# MOSFETs_and_Driver.net
KiCad netlist of a schematic drawn in Altium Designer
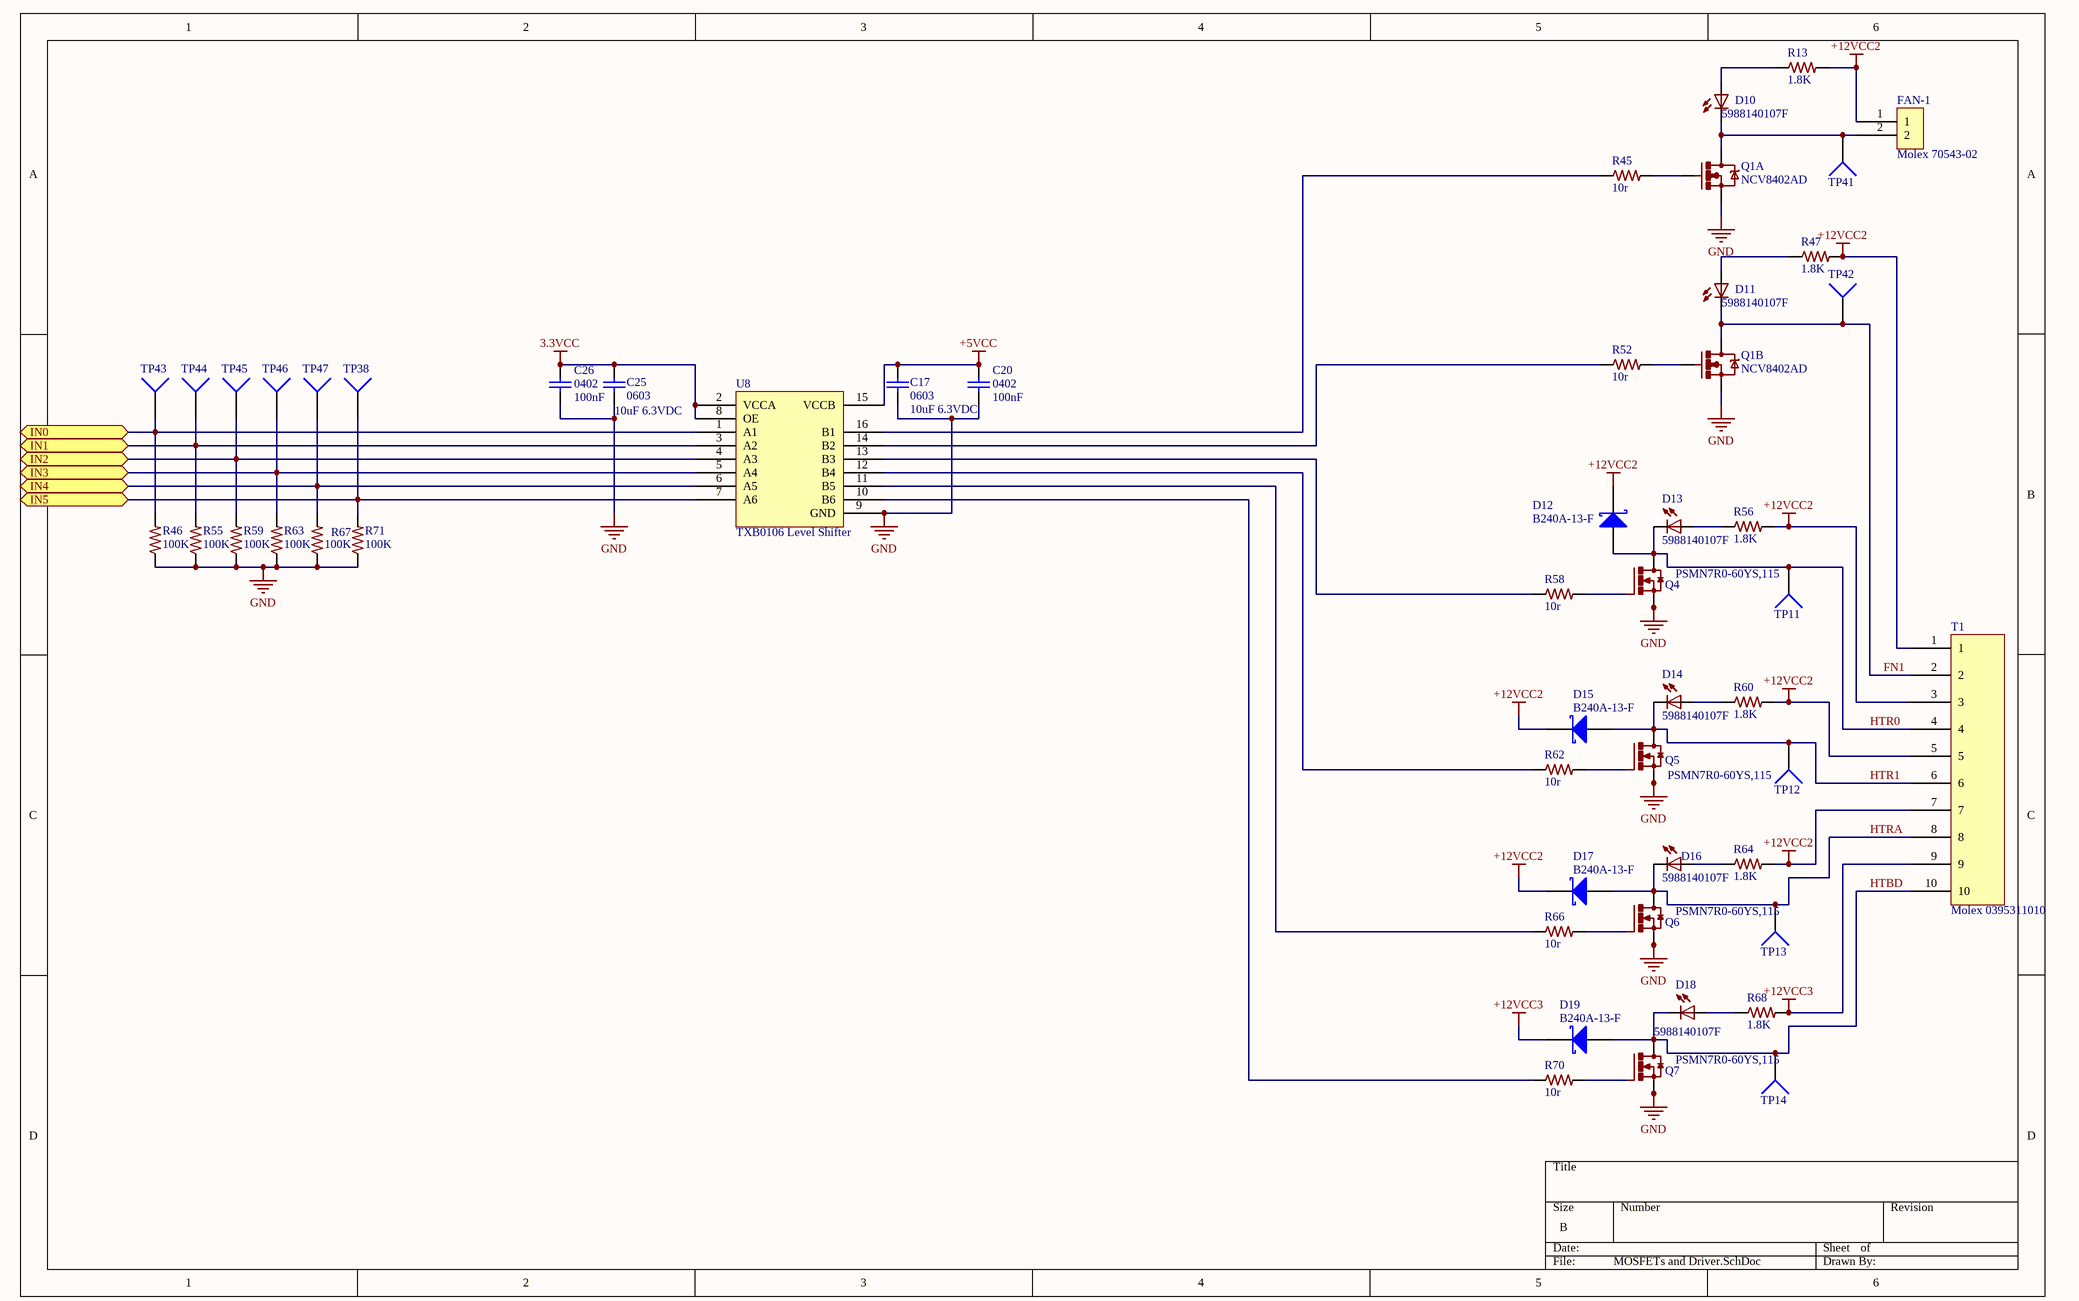
[diagram p0: MOSFETs and Driver.SchDoc]

(export (version "E")
  (design (tool "Eeschema 10.0.6"))
  (components
    (comp (ref "C17")
      (value "0603")
      (footprint "C0603")
      (description "CAP CER 10UF 6.3V 10% JB 0603")
      (fields
        (field (name "MFR PART #") "C1608JB0J106K080AB")
        (field (name "MFR") "TDK")
        (field (name "ALTIUM_VALUE") "10uF 6.3VDC")
      )
      (libsource (lib "Tigershark3D") (part "C1608JB0J106K080AB"))
    )
    (comp (ref "C20")
      (value "100nF")
      (footprint "C0402")
      (description "CAP CER 0.1UF (100nF) 16V 10% X7R 0402")
      (fields
        (field (name "MFR PART #") "GRM155R71C104KA88D")
        (field (name "MFR") "Murata")
        (field (name "PACKAGEREFERENCE") "0402")
        (field (name "PUBLISHER") "Ultimachine")
      )
      (libsource (lib "Tigershark3D") (part "GRM155R71C104KA88D"))
    )
    (comp (ref "C25")
      (value "0603")
      (footprint "C0603")
      (description "CAP CER 10UF 6.3V 10% JB 0603")
      (fields
        (field (name "MFR PART #") "C1608JB0J106K080AB")
        (field (name "MFR") "TDK")
        (field (name "ALTIUM_VALUE") "10uF 6.3VDC")
      )
      (libsource (lib "Tigershark3D") (part "C1608JB0J106K080AB"))
    )
    (comp (ref "C26")
      (value "100nF")
      (footprint "C0402")
      (description "CAP CER 0.1UF (100nF) 16V 10% X7R 0402")
      (fields
        (field (name "MFR PART #") "GRM155R71C104KA88D")
        (field (name "MFR") "Murata")
        (field (name "PACKAGEREFERENCE") "0402")
        (field (name "PUBLISHER") "Ultimachine")
      )
      (libsource (lib "Tigershark3D") (part "GRM155R71C104KA88D"))
    )
    (comp (ref "D10")
      (value "5988140107F")
      (footprint "LED2012120")
      (description "LED 0805 Yellow")
      (fields (field (name "PUBLISHER") "UltiMachine"))
      (libsource (lib "Tigershark3D") (part "5988140107F"))
    )
    (comp (ref "D11")
      (value "5988140107F")
      (footprint "LED2012120")
      (description "LED 0805 Yellow")
      (fields (field (name "PUBLISHER") "UltiMachine"))
      (libsource (lib "Tigershark3D") (part "5988140107F"))
    )
    (comp (ref "D12")
      (value "B240A-13-F")
      (footprint "SK310A-TP")
      (description "Schottky Diode")
      (fields (field (name "PUBLISHER") "Altium Limited"))
      (libsource (lib "Miscellaneous Devices") (part "D Schottky"))
    )
    (comp (ref "D13")
      (value "5988140107F")
      (footprint "LED2012120")
      (description "LED 0805 Yellow")
      (fields (field (name "PUBLISHER") "UltiMachine"))
      (libsource (lib "Tigershark3D") (part "5988140107F"))
    )
    (comp (ref "D14")
      (value "5988140107F")
      (footprint "LED2012120")
      (description "LED 0805 Yellow")
      (fields (field (name "PUBLISHER") "UltiMachine"))
      (libsource (lib "Tigershark3D") (part "5988140107F"))
    )
    (comp (ref "D15")
      (value "B240A-13-F")
      (footprint "SK310A-TP")
      (description "Schottky Diode")
      (fields (field (name "PUBLISHER") "Altium Limited"))
      (libsource (lib "Miscellaneous Devices") (part "D Schottky"))
    )
    (comp (ref "D16")
      (value "5988140107F")
      (footprint "LED2012120")
      (description "LED 0805 Yellow")
      (fields (field (name "PUBLISHER") "UltiMachine"))
      (libsource (lib "Tigershark3D") (part "5988140107F"))
    )
    (comp (ref "D17")
      (value "B240A-13-F")
      (footprint "SK310A-TP")
      (description "Schottky Diode")
      (fields (field (name "PUBLISHER") "Altium Limited"))
      (libsource (lib "Miscellaneous Devices") (part "D Schottky"))
    )
    (comp (ref "D18")
      (value "5988140107F")
      (footprint "LED2012120")
      (description "LED 0805 Yellow")
      (fields (field (name "PUBLISHER") "UltiMachine"))
      (libsource (lib "Tigershark3D") (part "5988140107F"))
    )
    (comp (ref "D19")
      (value "B240A-13-F")
      (footprint "SK310A-TP")
      (description "Schottky Diode")
      (fields (field (name "PUBLISHER") "Altium Limited"))
      (libsource (lib "Miscellaneous Devices") (part "D Schottky"))
    )
    (comp (ref "FAN-1")
      (value "Molex 70543-02")
      (footprint "70543-02")
      (libsource (lib "ZMBo Schematic Library") (part "Molex 70543-02"))
    )
    (comp (ref "Q1")
      (value "NCV8402AD")
      (footprint "NCV8402AD-SOIC8")
      (libsource (lib "3Delight") (part "NCV8402AD"))
    )
    (comp (ref "Q4")
      (value "PSMN7R0-60YS,115")
      (footprint "SOT669")
      (description "Mosfet N-channel 60V 356A 117W 9.3mOhms")
      (fields (field (name "PUBLISHER") "UltiMachine"))
      (libsource (lib "3Delight") (part "PSMN7R0-60YS,115"))
    )
    (comp (ref "Q5")
      (value "PSMN7R0-60YS,115")
      (footprint "SOT669")
      (description "Mosfet N-channel 60V 356A 117W 9.3mOhms")
      (fields (field (name "PUBLISHER") "UltiMachine"))
      (libsource (lib "3Delight") (part "PSMN7R0-60YS,115"))
    )
    (comp (ref "Q6")
      (value "PSMN7R0-60YS,115")
      (footprint "SOT669")
      (description "Mosfet N-channel 60V 356A 117W 9.3mOhms")
      (fields (field (name "PUBLISHER") "UltiMachine"))
      (libsource (lib "3Delight") (part "PSMN7R0-60YS,115"))
    )
    (comp (ref "Q7")
      (value "PSMN7R0-60YS,115")
      (footprint "SOT669")
      (description "Mosfet N-channel 60V 356A 117W 9.3mOhms")
      (fields (field (name "PUBLISHER") "UltiMachine"))
      (libsource (lib "3Delight") (part "PSMN7R0-60YS,115"))
    )
    (comp (ref "R13")
      (value "1.8K")
      (footprint "R0603")
      (description "RES 0603 1.8K 100mW 5%")
      (fields
        (field (name "MANUFACTURERPARTNUMBER") "RC0603JR-071K8L")
        (field (name "PUBLISHER") "UltiMachine")
      )
      (libsource (lib "Tigershark3D") (part "RC0603JR-071K8L"))
    )
    (comp (ref "R45")
      (value "10r")
      (footprint "R0603")
      (description "RES 0603 10r 100mW 1%")
      (fields
        (field (name "MANUFACTURERPARTNUMBER") "CRCW060310R0FKEA")
        (field (name "PUBLISHER") "UltiMachine")
      )
      (libsource (lib "Tigershark3D") (part "CRCW060310R0FKEA"))
    )
    (comp (ref "R46")
      (value "100K")
      (footprint "R0402")
      (description "RES SMD 100K OHM 1% 1/16W 0402")
      (fields
        (field (name "MANUFACTURER") "Samsung")
        (field (name "MANUFACTURERPARTNUMBER") "RC1005F104CS")
        (field (name "PUBLISHER") "UltiMachine")
      )
      (libsource (lib "Tigershark3D") (part "RC1005F104CS"))
    )
    (comp (ref "R47")
      (value "1.8K")
      (footprint "R0603")
      (description "RES 0603 1.8K 100mW 5%")
      (fields
        (field (name "MANUFACTURERPARTNUMBER") "RC0603JR-071K8L")
        (field (name "PUBLISHER") "UltiMachine")
      )
      (libsource (lib "Tigershark3D") (part "RC0603JR-071K8L"))
    )
    (comp (ref "R52")
      (value "10r")
      (footprint "R0603")
      (description "RES 0603 10r 100mW 1%")
      (fields
        (field (name "MANUFACTURERPARTNUMBER") "CRCW060310R0FKEA")
        (field (name "PUBLISHER") "UltiMachine")
      )
      (libsource (lib "Tigershark3D") (part "CRCW060310R0FKEA"))
    )
    (comp (ref "R55")
      (value "100K")
      (footprint "R0402")
      (description "RES SMD 100K OHM 1% 1/16W 0402")
      (fields
        (field (name "MANUFACTURER") "Samsung")
        (field (name "MANUFACTURERPARTNUMBER") "RC1005F104CS")
        (field (name "PUBLISHER") "UltiMachine")
      )
      (libsource (lib "Tigershark3D") (part "RC1005F104CS"))
    )
    (comp (ref "R56")
      (value "1.8K")
      (footprint "R0603")
      (description "RES 0603 1.8K 100mW 5%")
      (fields
        (field (name "MANUFACTURERPARTNUMBER") "RC0603JR-071K8L")
        (field (name "PUBLISHER") "UltiMachine")
      )
      (libsource (lib "Tigershark3D") (part "RC0603JR-071K8L"))
    )
    (comp (ref "R58")
      (value "10r")
      (footprint "R0603")
      (description "RES 0603 10r 100mW 1%")
      (fields
        (field (name "MANUFACTURERPARTNUMBER") "CRCW060310R0FKEA")
        (field (name "PUBLISHER") "UltiMachine")
      )
      (libsource (lib "Tigershark3D") (part "CRCW060310R0FKEA"))
    )
    (comp (ref "R59")
      (value "100K")
      (footprint "R0402")
      (description "RES SMD 100K OHM 1% 1/16W 0402")
      (fields
        (field (name "MANUFACTURER") "Samsung")
        (field (name "MANUFACTURERPARTNUMBER") "RC1005F104CS")
        (field (name "PUBLISHER") "UltiMachine")
      )
      (libsource (lib "Tigershark3D") (part "RC1005F104CS"))
    )
    (comp (ref "R60")
      (value "1.8K")
      (footprint "R0603")
      (description "RES 0603 1.8K 100mW 5%")
      (fields
        (field (name "MANUFACTURERPARTNUMBER") "RC0603JR-071K8L")
        (field (name "PUBLISHER") "UltiMachine")
      )
      (libsource (lib "Tigershark3D") (part "RC0603JR-071K8L"))
    )
    (comp (ref "R62")
      (value "10r")
      (footprint "R0603")
      (description "RES 0603 10r 100mW 1%")
      (fields
        (field (name "MANUFACTURERPARTNUMBER") "CRCW060310R0FKEA")
        (field (name "PUBLISHER") "UltiMachine")
      )
      (libsource (lib "Tigershark3D") (part "CRCW060310R0FKEA"))
    )
    (comp (ref "R63")
      (value "100K")
      (footprint "R0402")
      (description "RES SMD 100K OHM 1% 1/16W 0402")
      (fields
        (field (name "MANUFACTURER") "Samsung")
        (field (name "MANUFACTURERPARTNUMBER") "RC1005F104CS")
        (field (name "PUBLISHER") "UltiMachine")
      )
      (libsource (lib "Tigershark3D") (part "RC1005F104CS"))
    )
    (comp (ref "R64")
      (value "1.8K")
      (footprint "R0603")
      (description "RES 0603 1.8K 100mW 5%")
      (fields
        (field (name "MANUFACTURERPARTNUMBER") "RC0603JR-071K8L")
        (field (name "PUBLISHER") "UltiMachine")
      )
      (libsource (lib "Tigershark3D") (part "RC0603JR-071K8L"))
    )
    (comp (ref "R66")
      (value "10r")
      (footprint "R0603")
      (description "RES 0603 10r 100mW 1%")
      (fields
        (field (name "MANUFACTURERPARTNUMBER") "CRCW060310R0FKEA")
        (field (name "PUBLISHER") "UltiMachine")
      )
      (libsource (lib "Tigershark3D") (part "CRCW060310R0FKEA"))
    )
    (comp (ref "R67")
      (value "100K")
      (footprint "R0402")
      (description "RES SMD 100K OHM 1% 1/16W 0402")
      (fields
        (field (name "MANUFACTURER") "Samsung")
        (field (name "MANUFACTURERPARTNUMBER") "RC1005F104CS")
        (field (name "PUBLISHER") "UltiMachine")
      )
      (libsource (lib "Tigershark3D") (part "RC1005F104CS"))
    )
    (comp (ref "R68")
      (value "1.8K")
      (footprint "R0603")
      (description "RES 0603 1.8K 100mW 5%")
      (fields
        (field (name "MANUFACTURERPARTNUMBER") "RC0603JR-071K8L")
        (field (name "PUBLISHER") "UltiMachine")
      )
      (libsource (lib "Tigershark3D") (part "RC0603JR-071K8L"))
    )
    (comp (ref "R70")
      (value "10r")
      (footprint "R0603")
      (description "RES 0603 10r 100mW 1%")
      (fields
        (field (name "MANUFACTURERPARTNUMBER") "CRCW060310R0FKEA")
        (field (name "PUBLISHER") "UltiMachine")
      )
      (libsource (lib "Tigershark3D") (part "CRCW060310R0FKEA"))
    )
    (comp (ref "R71")
      (value "100K")
      (footprint "R0402")
      (description "RES SMD 100K OHM 1% 1/16W 0402")
      (fields
        (field (name "MANUFACTURER") "Samsung")
        (field (name "MANUFACTURERPARTNUMBER") "RC1005F104CS")
        (field (name "PUBLISHER") "UltiMachine")
      )
      (libsource (lib "Tigershark3D") (part "RC1005F104CS"))
    )
    (comp (ref "T1")
      (value "Molex 0395311010")
      (footprint "MSTBV10")
      (description "MSBTV10 10 port connector same as RAMBo")
      (fields (field (name "PART NUMBER") "0395311010"))
      (libsource (lib "Tigershark3D") (part "0395311010 - Molex 10 Position Connector"))
    )
    (comp (ref "TP11")
      (value "TP4")
      (footprint "TP-2")
      (description "Socket")
      (fields (field (name "PUBLISHER") "Altium Limited"))
      (libsource (lib "ZMBo Schematic Library") (part "Socket"))
    )
    (comp (ref "TP12")
      (value "TP4")
      (footprint "TP-2")
      (description "Socket")
      (fields (field (name "PUBLISHER") "Altium Limited"))
      (libsource (lib "ZMBo Schematic Library") (part "Socket"))
    )
    (comp (ref "TP13")
      (value "TP4")
      (footprint "TP-2")
      (description "Socket")
      (fields (field (name "PUBLISHER") "Altium Limited"))
      (libsource (lib "ZMBo Schematic Library") (part "Socket"))
    )
    (comp (ref "TP14")
      (value "TP4")
      (footprint "TP-2")
      (description "Socket")
      (fields (field (name "PUBLISHER") "Altium Limited"))
      (libsource (lib "ZMBo Schematic Library") (part "Socket"))
    )
    (comp (ref "TP38")
      (value "TP4")
      (footprint "TP-2")
      (description "Socket")
      (fields (field (name "PUBLISHER") "Altium Limited"))
      (libsource (lib "ZMBo Schematic Library") (part "Socket"))
    )
    (comp (ref "TP41")
      (value "TP4")
      (footprint "TP-2")
      (description "Socket")
      (fields (field (name "PUBLISHER") "Altium Limited"))
      (libsource (lib "ZMBo Schematic Library") (part "Socket"))
    )
    (comp (ref "TP42")
      (value "TP4")
      (footprint "TP-2")
      (description "Socket")
      (fields (field (name "PUBLISHER") "Altium Limited"))
      (libsource (lib "ZMBo Schematic Library") (part "Socket"))
    )
    (comp (ref "TP43")
      (value "TP4")
      (footprint "TP-2")
      (description "Socket")
      (fields (field (name "PUBLISHER") "Altium Limited"))
      (libsource (lib "ZMBo Schematic Library") (part "Socket"))
    )
    (comp (ref "TP44")
      (value "TP4")
      (footprint "TP-2")
      (description "Socket")
      (fields (field (name "PUBLISHER") "Altium Limited"))
      (libsource (lib "ZMBo Schematic Library") (part "Socket"))
    )
    (comp (ref "TP45")
      (value "TP4")
      (footprint "TP-2")
      (description "Socket")
      (fields (field (name "PUBLISHER") "Altium Limited"))
      (libsource (lib "ZMBo Schematic Library") (part "Socket"))
    )
    (comp (ref "TP46")
      (value "TP4")
      (footprint "TP-2")
      (description "Socket")
      (fields (field (name "PUBLISHER") "Altium Limited"))
      (libsource (lib "ZMBo Schematic Library") (part "Socket"))
    )
    (comp (ref "TP47")
      (value "TP4")
      (footprint "TP-2")
      (description "Socket")
      (fields (field (name "PUBLISHER") "Altium Limited"))
      (libsource (lib "ZMBo Schematic Library") (part "Socket"))
    )
    (comp (ref "U8")
      (value "TXB0106 Level Shifter")
      (footprint "TSOP65P640X120-16N")
      (description "TXB0106 - Bidriectional Opendrain/pushpull level shift")
      (libsource (lib "ZMBo Schematic Library") (part "TXB0106"))
    )
  )
  (nets
    (net (code "1") (name "+5VCC") (class "Default")
      (node (ref "C17") (pin "2") (pinfunction "2_2") (pintype "passive"))
      (node (ref "C20") (pin "2") (pinfunction "2_2") (pintype "passive"))
      (node (ref "U8") (pin "15") (pinfunction "VCCB_15") (pintype "passive"))
    )
    (net (code "2") (name "+12VCC2") (class "Default")
      (node (ref "D12") (pin "2") (pinfunction "K_2") (pintype "passive"))
      (node (ref "D15") (pin "2") (pinfunction "K_2") (pintype "passive"))
      (node (ref "D17") (pin "2") (pinfunction "K_2") (pintype "passive"))
      (node (ref "FAN-1") (pin "1") (pinfunction "1_1") (pintype "passive"))
      (node (ref "R13") (pin "2") (pinfunction "2_2") (pintype "passive"))
      (node (ref "R47") (pin "2") (pinfunction "2_2") (pintype "passive"))
      (node (ref "R56") (pin "2") (pinfunction "2_2") (pintype "passive"))
      (node (ref "R60") (pin "2") (pinfunction "2_2") (pintype "passive"))
      (node (ref "R64") (pin "2") (pinfunction "2_2") (pintype "passive"))
      (node (ref "T1") (pin "1") (pinfunction "1_1") (pintype "passive"))
      (node (ref "T1") (pin "3") (pinfunction "3_3") (pintype "passive"))
      (node (ref "T1") (pin "5") (pinfunction "5_5") (pintype "passive"))
      (node (ref "T1") (pin "7") (pinfunction "7_7") (pintype "passive"))
    )
    (net (code "3") (name "+12VCC3") (class "Default")
      (node (ref "D19") (pin "2") (pinfunction "K_2") (pintype "passive"))
      (node (ref "R68") (pin "2") (pinfunction "2_2") (pintype "passive"))
      (node (ref "T1") (pin "9") (pinfunction "9_9") (pintype "passive"))
    )
    (net (code "4") (name "/FN1") (class "Default")
      (node (ref "D11") (pin "C") (pinfunction "C_C") (pintype "passive"))
      (node (ref "Q1") (pin "5") (pinfunction "D_5") (pintype "passive"))
      (node (ref "T1") (pin "2") (pinfunction "2_2") (pintype "passive"))
      (node (ref "TP42") (pin "1") (pinfunction "1_1") (pintype "passive"))
    )
    (net (code "5") (name "/HTBD") (class "Default")
      (node (ref "D18") (pin "C") (pinfunction "C_C") (pintype "passive"))
      (node (ref "D19") (pin "1") (pinfunction "A_1") (pintype "passive"))
      (node (ref "Q7") (pin "MB") (pinfunction "D_MB") (pintype "passive"))
      (node (ref "T1") (pin "10") (pinfunction "10_10") (pintype "passive"))
      (node (ref "TP14") (pin "1") (pinfunction "1_1") (pintype "passive"))
    )
    (net (code "6") (name "/HTR0") (class "Default")
      (node (ref "D12") (pin "1") (pinfunction "A_1") (pintype "passive"))
      (node (ref "D13") (pin "C") (pinfunction "C_C") (pintype "passive"))
      (node (ref "Q4") (pin "MB") (pinfunction "D_MB") (pintype "passive"))
      (node (ref "T1") (pin "4") (pinfunction "4_4") (pintype "passive"))
      (node (ref "TP11") (pin "1") (pinfunction "1_1") (pintype "passive"))
    )
    (net (code "7") (name "/HTR1") (class "Default")
      (node (ref "D14") (pin "C") (pinfunction "C_C") (pintype "passive"))
      (node (ref "D15") (pin "1") (pinfunction "A_1") (pintype "passive"))
      (node (ref "Q5") (pin "MB") (pinfunction "D_MB") (pintype "passive"))
      (node (ref "T1") (pin "6") (pinfunction "6_6") (pintype "passive"))
      (node (ref "TP12") (pin "1") (pinfunction "1_1") (pintype "passive"))
    )
    (net (code "8") (name "/HTRA") (class "Default")
      (node (ref "D16") (pin "C") (pinfunction "C_C") (pintype "passive"))
      (node (ref "D17") (pin "1") (pinfunction "A_1") (pintype "passive"))
      (node (ref "Q6") (pin "MB") (pinfunction "D_MB") (pintype "passive"))
      (node (ref "T1") (pin "8") (pinfunction "8_8") (pintype "passive"))
      (node (ref "TP13") (pin "1") (pinfunction "1_1") (pintype "passive"))
    )
    (net (code "9") (name "/IN0") (class "Default")
      (node (ref "R46") (pin "2") (pinfunction "2_2") (pintype "passive"))
      (node (ref "TP43") (pin "1") (pinfunction "1_1") (pintype "passive"))
      (node (ref "U8") (pin "1") (pinfunction "A1_1") (pintype "passive"))
    )
    (net (code "10") (name "/IN1") (class "Default")
      (node (ref "R55") (pin "2") (pinfunction "2_2") (pintype "passive"))
      (node (ref "TP44") (pin "1") (pinfunction "1_1") (pintype "passive"))
      (node (ref "U8") (pin "3") (pinfunction "A2_3") (pintype "passive"))
    )
    (net (code "11") (name "/IN2") (class "Default")
      (node (ref "R59") (pin "2") (pinfunction "2_2") (pintype "passive"))
      (node (ref "TP45") (pin "1") (pinfunction "1_1") (pintype "passive"))
      (node (ref "U8") (pin "4") (pinfunction "A3_4") (pintype "passive"))
    )
    (net (code "12") (name "/IN3") (class "Default")
      (node (ref "R63") (pin "2") (pinfunction "2_2") (pintype "passive"))
      (node (ref "TP46") (pin "1") (pinfunction "1_1") (pintype "passive"))
      (node (ref "U8") (pin "5") (pinfunction "A4_5") (pintype "passive"))
    )
    (net (code "13") (name "/IN4") (class "Default")
      (node (ref "R67") (pin "2") (pinfunction "2_2") (pintype "passive"))
      (node (ref "TP47") (pin "1") (pinfunction "1_1") (pintype "passive"))
      (node (ref "U8") (pin "6") (pinfunction "A5_6") (pintype "passive"))
    )
    (net (code "14") (name "/IN5") (class "Default")
      (node (ref "R71") (pin "2") (pinfunction "2_2") (pintype "passive"))
      (node (ref "TP38") (pin "1") (pinfunction "1_1") (pintype "passive"))
      (node (ref "U8") (pin "7") (pinfunction "A6_7") (pintype "passive"))
    )
    (net (code "15") (name "3.3VCC") (class "Default")
      (node (ref "C25") (pin "2") (pinfunction "2_2") (pintype "passive"))
      (node (ref "C26") (pin "2") (pinfunction "2_2") (pintype "passive"))
      (node (ref "U8") (pin "2") (pinfunction "VCCA_2") (pintype "passive"))
      (node (ref "U8") (pin "8") (pinfunction "OE_8") (pintype "passive"))
    )
    (net (code "16") (name "GND") (class "Default")
      (node (ref "C17") (pin "1") (pinfunction "1_1") (pintype "passive"))
      (node (ref "C20") (pin "1") (pinfunction "1_1") (pintype "passive"))
      (node (ref "C25") (pin "1") (pinfunction "1_1") (pintype "passive"))
      (node (ref "C26") (pin "1") (pinfunction "1_1") (pintype "passive"))
      (node (ref "Q1") (pin "1") (pinfunction "S_1") (pintype "passive"))
      (node (ref "Q1") (pin "3") (pinfunction "S_3") (pintype "passive"))
      (node (ref "Q4") (pin "1") (pinfunction "S_1") (pintype "passive"))
      (node (ref "Q4") (pin "2") (pinfunction "S_2") (pintype "passive"))
      (node (ref "Q4") (pin "3") (pinfunction "S_3") (pintype "passive"))
      (node (ref "Q5") (pin "1") (pinfunction "S_1") (pintype "passive"))
      (node (ref "Q5") (pin "2") (pinfunction "S_2") (pintype "passive"))
      (node (ref "Q5") (pin "3") (pinfunction "S_3") (pintype "passive"))
      (node (ref "Q6") (pin "1") (pinfunction "S_1") (pintype "passive"))
      (node (ref "Q6") (pin "2") (pinfunction "S_2") (pintype "passive"))
      (node (ref "Q6") (pin "3") (pinfunction "S_3") (pintype "passive"))
      (node (ref "Q7") (pin "1") (pinfunction "S_1") (pintype "passive"))
      (node (ref "Q7") (pin "2") (pinfunction "S_2") (pintype "passive"))
      (node (ref "Q7") (pin "3") (pinfunction "S_3") (pintype "passive"))
      (node (ref "R46") (pin "1") (pinfunction "1_1") (pintype "passive"))
      (node (ref "R55") (pin "1") (pinfunction "1_1") (pintype "passive"))
      (node (ref "R59") (pin "1") (pinfunction "1_1") (pintype "passive"))
      (node (ref "R63") (pin "1") (pinfunction "1_1") (pintype "passive"))
      (node (ref "R67") (pin "1") (pinfunction "1_1") (pintype "passive"))
      (node (ref "R71") (pin "1") (pinfunction "1_1") (pintype "passive"))
      (node (ref "U8") (pin "9") (pinfunction "GND_9") (pintype "passive"))
    )
    (net (code "17") (name "Net-(D10-PadA)") (class "Default")
      (node (ref "D10") (pin "A") (pinfunction "A_A") (pintype "passive"))
      (node (ref "R13") (pin "1") (pinfunction "1_1") (pintype "passive"))
    )
    (net (code "18") (name "Net-(D11-PadA)") (class "Default")
      (node (ref "D11") (pin "A") (pinfunction "A_A") (pintype "passive"))
      (node (ref "R47") (pin "1") (pinfunction "1_1") (pintype "passive"))
    )
    (net (code "19") (name "Net-(D13-PadA)") (class "Default")
      (node (ref "D13") (pin "A") (pinfunction "A_A") (pintype "passive"))
      (node (ref "R56") (pin "1") (pinfunction "1_1") (pintype "passive"))
    )
    (net (code "20") (name "Net-(D14-PadA)") (class "Default")
      (node (ref "D14") (pin "A") (pinfunction "A_A") (pintype "passive"))
      (node (ref "R60") (pin "1") (pinfunction "1_1") (pintype "passive"))
    )
    (net (code "21") (name "Net-(D16-PadA)") (class "Default")
      (node (ref "D16") (pin "A") (pinfunction "A_A") (pintype "passive"))
      (node (ref "R64") (pin "1") (pinfunction "1_1") (pintype "passive"))
    )
    (net (code "22") (name "Net-(D18-PadA)") (class "Default")
      (node (ref "D18") (pin "A") (pinfunction "A_A") (pintype "passive"))
      (node (ref "R68") (pin "1") (pinfunction "1_1") (pintype "passive"))
    )
    (net (code "23") (name "Net-(Q1A-D)") (class "Default")
      (node (ref "D10") (pin "C") (pinfunction "C_C") (pintype "passive"))
      (node (ref "FAN-1") (pin "2") (pinfunction "2_2") (pintype "passive"))
      (node (ref "Q1") (pin "7") (pinfunction "D_7") (pintype "passive"))
      (node (ref "TP41") (pin "1") (pinfunction "1_1") (pintype "passive"))
    )
    (net (code "24") (name "Net-(Q1A-G)") (class "Default")
      (node (ref "Q1") (pin "2") (pinfunction "G_2") (pintype "passive"))
      (node (ref "R45") (pin "2") (pinfunction "2_2") (pintype "passive"))
    )
    (net (code "25") (name "Net-(Q1B-G)") (class "Default")
      (node (ref "Q1") (pin "4") (pinfunction "G_4") (pintype "passive"))
      (node (ref "R52") (pin "2") (pinfunction "2_2") (pintype "passive"))
    )
    (net (code "26") (name "Net-(Q4-G)") (class "Default")
      (node (ref "Q4") (pin "4") (pinfunction "G_4") (pintype "passive"))
      (node (ref "R58") (pin "2") (pinfunction "2_2") (pintype "passive"))
    )
    (net (code "27") (name "Net-(Q5-G)") (class "Default")
      (node (ref "Q5") (pin "4") (pinfunction "G_4") (pintype "passive"))
      (node (ref "R62") (pin "2") (pinfunction "2_2") (pintype "passive"))
    )
    (net (code "28") (name "Net-(Q6-G)") (class "Default")
      (node (ref "Q6") (pin "4") (pinfunction "G_4") (pintype "passive"))
      (node (ref "R66") (pin "2") (pinfunction "2_2") (pintype "passive"))
    )
    (net (code "29") (name "Net-(Q7-G)") (class "Default")
      (node (ref "Q7") (pin "4") (pinfunction "G_4") (pintype "passive"))
      (node (ref "R70") (pin "2") (pinfunction "2_2") (pintype "passive"))
    )
    (net (code "30") (name "Net-(U8-B1)") (class "Default")
      (node (ref "R45") (pin "1") (pinfunction "1_1") (pintype "passive"))
      (node (ref "U8") (pin "16") (pinfunction "B1_16") (pintype "passive"))
    )
    (net (code "31") (name "Net-(U8-B2)") (class "Default")
      (node (ref "R52") (pin "1") (pinfunction "1_1") (pintype "passive"))
      (node (ref "U8") (pin "14") (pinfunction "B2_14") (pintype "passive"))
    )
    (net (code "32") (name "Net-(U8-B3)") (class "Default")
      (node (ref "R58") (pin "1") (pinfunction "1_1") (pintype "passive"))
      (node (ref "U8") (pin "13") (pinfunction "B3_13") (pintype "passive"))
    )
    (net (code "33") (name "Net-(U8-B4)") (class "Default")
      (node (ref "R62") (pin "1") (pinfunction "1_1") (pintype "passive"))
      (node (ref "U8") (pin "12") (pinfunction "B4_12") (pintype "passive"))
    )
    (net (code "34") (name "Net-(U8-B5)") (class "Default")
      (node (ref "R66") (pin "1") (pinfunction "1_1") (pintype "passive"))
      (node (ref "U8") (pin "11") (pinfunction "B5_11") (pintype "passive"))
    )
    (net (code "35") (name "Net-(U8-B6)") (class "Default")
      (node (ref "R70") (pin "1") (pinfunction "1_1") (pintype "passive"))
      (node (ref "U8") (pin "10") (pinfunction "B6_10") (pintype "passive"))
    )
  )
)
